# SFP.net
KiCad netlist of a schematic drawn in Altium Designer
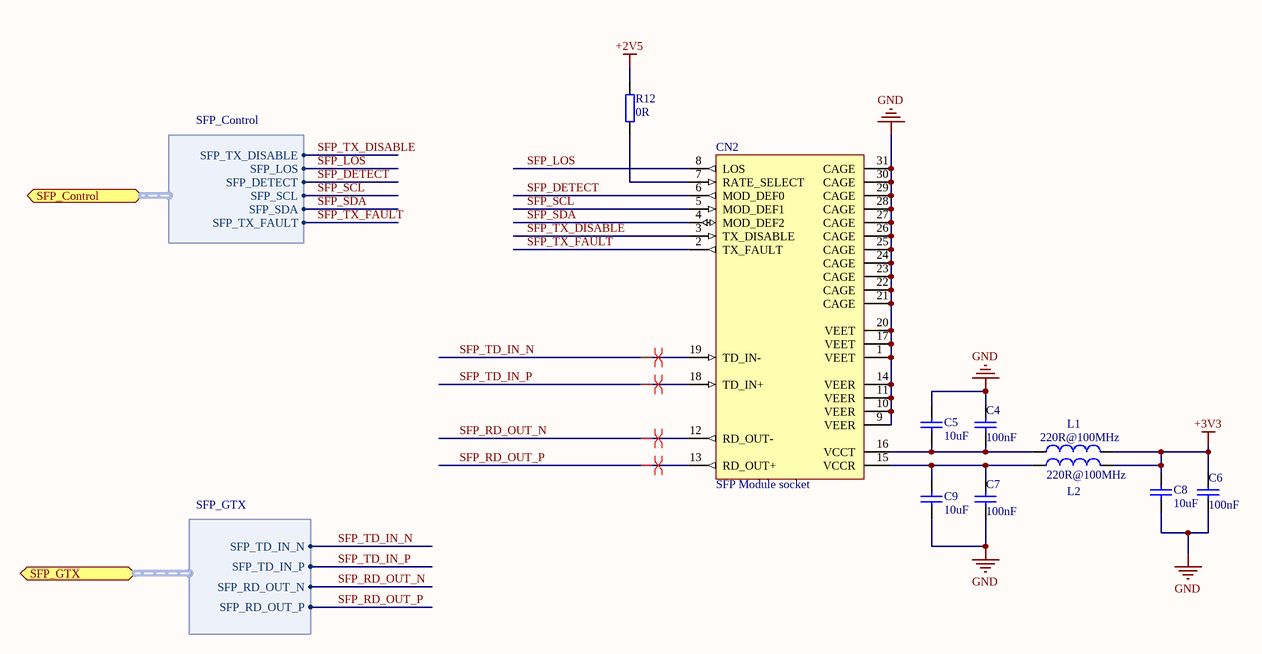
[diagram p0: SFP.SchDoc]

(export (version "E")
  (design (tool "Eeschema 10.0.6"))
  (components
    (comp (ref "C4")
      (value "100nF")
      (footprint "CC1608-0603")
      (description "Capacitor")
      (fields
        (field (name "TOLERANCE") "±10%")
        (field (name "VOLTAGE") "16V")
        (field (name "PUBLISHER") "Altium Limited")
      )
      (libsource (lib "wr_switch") (part "Cap"))
    )
    (comp (ref "C5")
      (value "10uF")
      (footprint "CC1608-0603")
      (description "Capacitor")
      (fields
        (field (name "TOLERANCE") "±20%")
        (field (name "VOLTAGE") "6.3V")
        (field (name "PUBLISHER") "Altium Limited")
      )
      (libsource (lib "wr_switch") (part "Cap"))
    )
    (comp (ref "C6")
      (value "100nF")
      (footprint "CC1608-0603")
      (description "Capacitor")
      (fields
        (field (name "TOLERANCE") "±10%")
        (field (name "VOLTAGE") "16V")
        (field (name "PUBLISHER") "Altium Limited")
      )
      (libsource (lib "wr_switch") (part "Cap"))
    )
    (comp (ref "C7")
      (value "100nF")
      (footprint "CC1608-0603")
      (description "Capacitor")
      (fields
        (field (name "TOLERANCE") "±10%")
        (field (name "VOLTAGE") "16V")
        (field (name "PUBLISHER") "Altium Limited")
      )
      (libsource (lib "wr_switch") (part "Cap"))
    )
    (comp (ref "C8")
      (value "10uF")
      (footprint "CC1608-0603")
      (description "Capacitor")
      (fields
        (field (name "TOLERANCE") "±20%")
        (field (name "VOLTAGE") "6.3V")
        (field (name "PUBLISHER") "Altium Limited")
      )
      (libsource (lib "wr_switch") (part "Cap"))
    )
    (comp (ref "C9")
      (value "10uF")
      (footprint "CC1608-0603")
      (description "Capacitor")
      (fields
        (field (name "TOLERANCE") "±20%")
        (field (name "VOLTAGE") "6.3V")
        (field (name "PUBLISHER") "Altium Limited")
      )
      (libsource (lib "wr_switch") (part "Cap"))
    )
    (comp (ref "CN2")
      (value "SFP Module socket")
      (footprint "7S_WR:SFP_SINGLE_PORT")
      (description "Socket for SFP module")
      (libsource (lib "wr_switch") (part "SFP_SOCKET_SINGLE"))
    )
    (comp (ref "L1")
      (value "220R@100MHz Ferrite Bead")
      (footprint "0603")
      (description "ferrite bead")
      (fields (field (name "IMPEDANCE") "220R@100MHz"))
      (libsource (lib "wr_switch") (part "L_FERRITE_BEAD"))
    )
    (comp (ref "L2")
      (value "220R@100MHz Ferrite Bead")
      (footprint "0603")
      (description "ferrite bead")
      (fields (field (name "IMPEDANCE") "220R@100MHz"))
      (libsource (lib "wr_switch") (part "L_FERRITE_BEAD"))
    )
    (comp (ref "R12")
      (value "0R")
      (footprint "0603")
      (description "SMD Resistor")
      (libsource (lib "wr_switch") (part "RES_SMD"))
    )
  )
  (nets
    (net (code "3") (name "+2V5") (class "Default")
      (node (ref "R12") (pin "1") (pinfunction "1_1") (pintype "passive"))
    )
    (net (code "4") (name "+3V3") (class "Default")
      (node (ref "C6") (pin "1") (pinfunction "1_1") (pintype "passive"))
      (node (ref "C8") (pin "1") (pinfunction "1_1") (pintype "passive"))
      (node (ref "L1") (pin "2") (pinfunction "2_2") (pintype "passive"))
      (node (ref "L2") (pin "2") (pinfunction "2_2") (pintype "passive"))
    )
    (net (code "5") (name "/SFP_DETECT") (class "Default")
      (node (ref "CN2") (pin "6") (pinfunction "MOD_DEF0_6") (pintype "output"))
    )
    (net (code "6") (name "/SFP_LOS") (class "Default")
      (node (ref "CN2") (pin "8") (pinfunction "LOS_8") (pintype "output"))
    )
    (net (code "7") (name "/SFP_RD_OUT_N") (class "Default")
      (node (ref "CN2") (pin "12") (pinfunction "RD_OUT-_12") (pintype "output"))
    )
    (net (code "8") (name "/SFP_RD_OUT_P") (class "Default")
      (node (ref "CN2") (pin "13") (pinfunction "RD_OUT+_13") (pintype "output"))
    )
    (net (code "9") (name "/SFP_SCL") (class "Default")
      (node (ref "CN2") (pin "5") (pinfunction "MOD_DEF1_5") (pintype "input"))
    )
    (net (code "10") (name "/SFP_SDA") (class "Default")
      (node (ref "CN2") (pin "4") (pinfunction "MOD_DEF2_4") (pintype "bidirectional"))
    )
    (net (code "11") (name "/SFP_TD_IN_N") (class "Default")
      (node (ref "CN2") (pin "19") (pinfunction "TD_IN-_19") (pintype "input"))
    )
    (net (code "12") (name "/SFP_TD_IN_P") (class "Default")
      (node (ref "CN2") (pin "18") (pinfunction "TD_IN+_18") (pintype "input"))
    )
    (net (code "13") (name "/SFP_TX_DISABLE") (class "Default")
      (node (ref "CN2") (pin "3") (pinfunction "TX_DISABLE_3") (pintype "input"))
    )
    (net (code "14") (name "/SFP_TX_FAULT") (class "Default")
      (node (ref "CN2") (pin "2") (pinfunction "TX_FAULT_2") (pintype "output"))
    )
    (net (code "17") (name "GND") (class "Default")
      (node (ref "C4") (pin "1") (pinfunction "1_1") (pintype "passive"))
      (node (ref "C5") (pin "1") (pinfunction "1_1") (pintype "passive"))
      (node (ref "C6") (pin "2") (pinfunction "2_2") (pintype "passive"))
      (node (ref "C7") (pin "2") (pinfunction "2_2") (pintype "passive"))
      (node (ref "C8") (pin "2") (pinfunction "2_2") (pintype "passive"))
      (node (ref "C9") (pin "2") (pinfunction "2_2") (pintype "passive"))
      (node (ref "CN2") (pin "1") (pinfunction "VEET_1") (pintype "power_in"))
      (node (ref "CN2") (pin "10") (pinfunction "VEER_10") (pintype "power_in"))
      (node (ref "CN2") (pin "11") (pinfunction "VEER_11") (pintype "power_in"))
      (node (ref "CN2") (pin "14") (pinfunction "VEER_14") (pintype "power_in"))
      (node (ref "CN2") (pin "17") (pinfunction "VEET_17") (pintype "power_in"))
      (node (ref "CN2") (pin "20") (pinfunction "VEET_20") (pintype "power_in"))
      (node (ref "CN2") (pin "21") (pinfunction "CAGE_21") (pintype "power_in"))
      (node (ref "CN2") (pin "22") (pinfunction "CAGE_22") (pintype "power_in"))
      (node (ref "CN2") (pin "23") (pinfunction "CAGE_23") (pintype "power_in"))
      (node (ref "CN2") (pin "24") (pinfunction "CAGE_24") (pintype "power_in"))
      (node (ref "CN2") (pin "25") (pinfunction "CAGE_25") (pintype "power_in"))
      (node (ref "CN2") (pin "26") (pinfunction "CAGE_26") (pintype "power_in"))
      (node (ref "CN2") (pin "27") (pinfunction "CAGE_27") (pintype "power_in"))
      (node (ref "CN2") (pin "28") (pinfunction "CAGE_28") (pintype "power_in"))
      (node (ref "CN2") (pin "29") (pinfunction "CAGE_29") (pintype "power_in"))
      (node (ref "CN2") (pin "30") (pinfunction "CAGE_30") (pintype "power_in"))
      (node (ref "CN2") (pin "31") (pinfunction "CAGE_31") (pintype "power_in"))
      (node (ref "CN2") (pin "9") (pinfunction "VEER_9") (pintype "power_in"))
    )
    (net (code "18") (name "Net-(CN2-RATE_SELECT)") (class "Default")
      (node (ref "CN2") (pin "7") (pinfunction "RATE_SELECT_7") (pintype "input"))
      (node (ref "R12") (pin "2") (pinfunction "2_2") (pintype "passive"))
    )
    (net (code "19") (name "Net-(CN2-VCCR)") (class "Default")
      (node (ref "C7") (pin "1") (pinfunction "1_1") (pintype "passive"))
      (node (ref "C9") (pin "1") (pinfunction "1_1") (pintype "passive"))
      (node (ref "CN2") (pin "15") (pinfunction "VCCR_15") (pintype "power_in"))
      (node (ref "L2") (pin "1") (pinfunction "1_1") (pintype "passive"))
    )
    (net (code "20") (name "Net-(CN2-VCCT)") (class "Default")
      (node (ref "C4") (pin "2") (pinfunction "2_2") (pintype "passive"))
      (node (ref "C5") (pin "2") (pinfunction "2_2") (pintype "passive"))
      (node (ref "CN2") (pin "16") (pinfunction "VCCT_16") (pintype "power_in"))
      (node (ref "L1") (pin "1") (pinfunction "1_1") (pintype "passive"))
    )
  )
)
